# ExpectoPatronum10.net
KiCad netlist of a schematic drawn in EAGLE
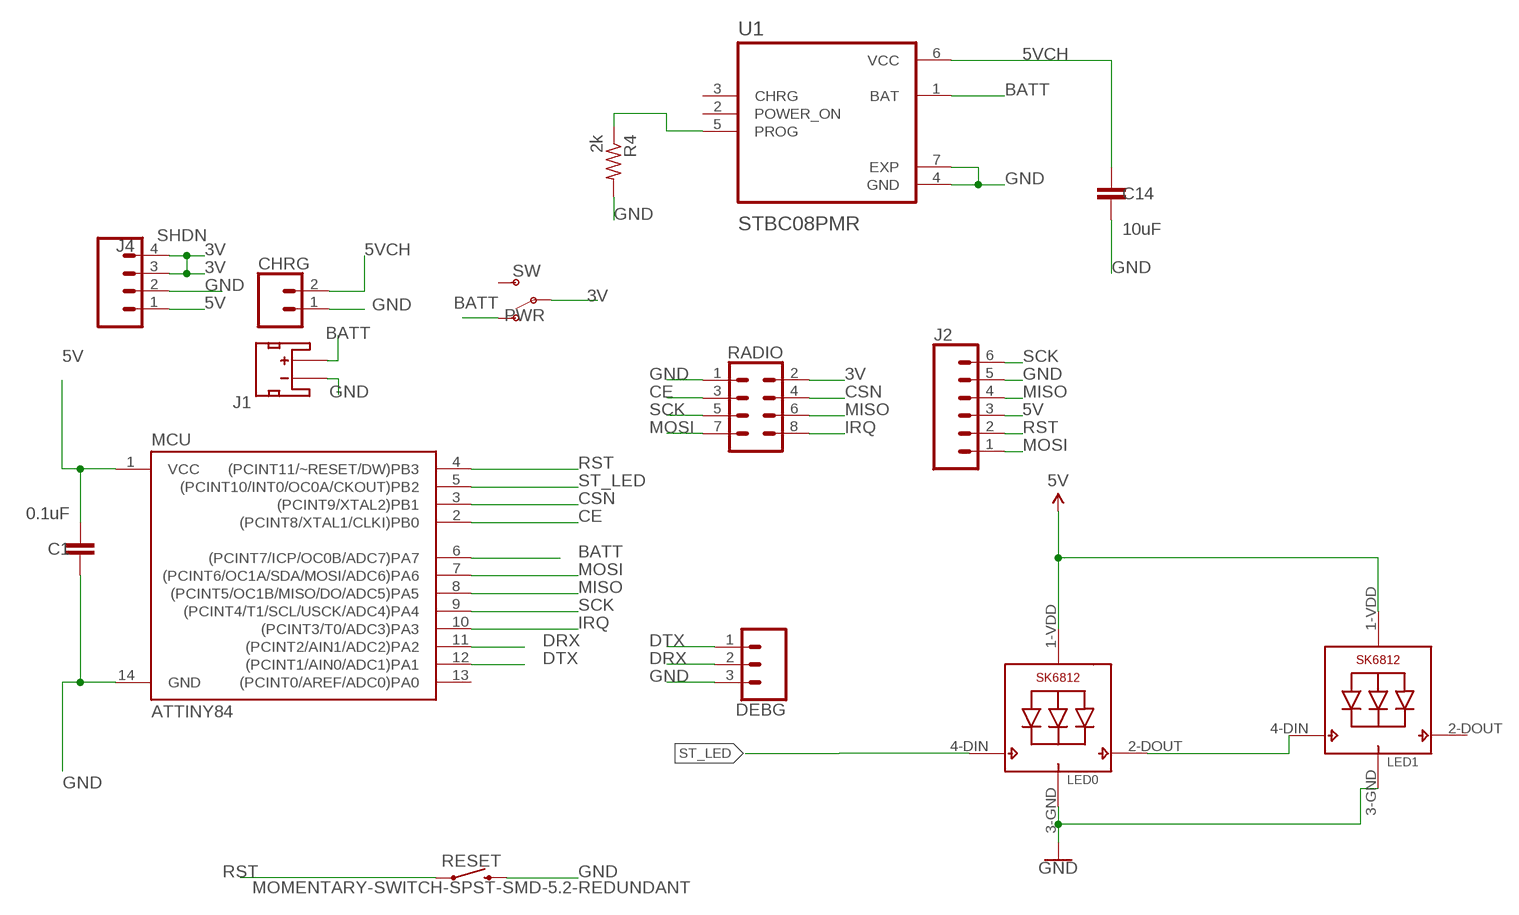
[diagram p0: schematic, sheet 1]

(export (version "E")
  (design (tool "Eeschema 10.0.6"))
  (components
    (comp (ref "C1")
      (value "0.1uF")
      (footprint "eagle-import:0603")
      (libsource (lib "eagle-import") (part "0.1UF-0603-25V-5%"))
    )
    (comp (ref "C14")
      (value "10uF")
      (footprint "eagle-import:0603")
      (libsource (lib "eagle-import") (part "10UF-0603-6.3V-20%"))
    )
    (comp (ref "CHRG")
      (value "CONN_02")
      (footprint "eagle-import:1X02")
      (libsource (lib "eagle-import") (part "CONN_02"))
    )
    (comp (ref "DEBG")
      (value "CONN_03")
      (footprint "eagle-import:1X03")
      (libsource (lib "eagle-import") (part "CONN_03"))
    )
    (comp (ref "J1")
      (value "JST_2MM_MALE")
      (footprint "eagle-import:JST-2-SMD")
      (libsource (lib "eagle-import") (part "JST_2MM_MALE"))
    )
    (comp (ref "J2")
      (value "CONN_06NO_SILK_FEMALE_PTH")
      (footprint "eagle-import:1X06_NO_SILK")
      (libsource (lib "eagle-import") (part "CONN_06NO_SILK_FEMALE_PTH"))
    )
    (comp (ref "J4")
      (value "CONN_04")
      (footprint "eagle-import:1X04")
      (libsource (lib "eagle-import") (part "CONN_04"))
    )
    (comp (ref "LED0")
      (value "SK6812_5050W")
      (footprint "eagle-import:LED5050_W")
      (libsource (lib "eagle-import") (part "SK6812_5050W"))
    )
    (comp (ref "LED1")
      (value "SK6812_5050W")
      (footprint "eagle-import:LED5050_W")
      (libsource (lib "eagle-import") (part "SK6812_5050W"))
    )
    (comp (ref "MCU")
      (value "ATTINY84")
      (footprint "eagle-import:SO14")
      (libsource (lib "eagle-import") (part "ATTINY84"))
    )
    (comp (ref "PWR")
      (value "SW")
      (footprint "eagle-import:SWITCH_SPST_SMD_A")
      (libsource (lib "eagle-import") (part "SWITCH-SPDT-SMD-RIGHT-ANGLE"))
    )
    (comp (ref "R4")
      (value "2k")
      (footprint "eagle-import:R0603")
      (libsource (lib "eagle-import") (part "R-US_R0603"))
    )
    (comp (ref "RADIO")
      (value "CONN_04X2")
      (footprint "eagle-import:2X4")
      (libsource (lib "eagle-import") (part "CONN_04X2"))
    )
    (comp (ref "RESET")
      (value "MOMENTARY-SWITCH-SPST-SMD-5.2-REDUNDANT")
      (footprint "eagle-import:TACTILE_SWITCH_SMD_5.2MM")
      (libsource (lib "eagle-import") (part "MOMENTARY-SWITCH-SPST-SMD-5.2-REDUNDANT"))
    )
    (comp (ref "U1")
      (value "STBC08PMR")
      (footprint "eagle-import:SON95P300X300X100-7N")
      (fields (field (name "DIGI-KEY_PART_NUMBER") "497-5808-1-ND") (field (name "MF") "STMicroelectronics"))
      (libsource (lib "eagle-import") (part "STBC08PMR"))
    )
  )
  (nets
    (net (code "1") (name "/3V") (class "Default")
      (node (ref "J4") (pin "3") (pinfunction "3_3") (pintype "passive"))
      (node (ref "J4") (pin "4") (pinfunction "4_4") (pintype "passive"))
      (node (ref "PWR") (pin "2") (pinfunction "P_2") (pintype "passive"))
      (node (ref "RADIO") (pin "2") (pinfunction "2_2") (pintype "passive"))
    )
    (net (code "2") (name "/5VCH") (class "Default")
      (node (ref "C14") (pin "1") (pinfunction "1_1") (pintype "passive"))
      (node (ref "CHRG") (pin "2") (pinfunction "2_2") (pintype "passive"))
      (node (ref "U1") (pin "6") (pinfunction "VCC_6") (pintype "power_in"))
    )
    (net (code "3") (name "/BATT") (class "Default")
      (node (ref "J1") (pin "2") (pinfunction "+_2") (pintype "bidirectional"))
      (node (ref "MCU") (pin "6") (pinfunction "(PCINT7/ICP/OC0B/ADC7)PA7_6") (pintype "bidirectional"))
      (node (ref "PWR") (pin "1") (pinfunction "O_1") (pintype "passive"))
      (node (ref "U1") (pin "1") (pinfunction "BAT_1") (pintype "output"))
    )
    (net (code "4") (name "/CE") (class "Default")
      (node (ref "MCU") (pin "2") (pinfunction "(PCINT8/XTAL1/CLKI)PB0_2") (pintype "bidirectional"))
      (node (ref "RADIO") (pin "3") (pinfunction "3_3") (pintype "passive"))
    )
    (net (code "5") (name "/CSN") (class "Default")
      (node (ref "MCU") (pin "3") (pinfunction "(PCINT9/XTAL2)PB1_3") (pintype "bidirectional"))
      (node (ref "RADIO") (pin "4") (pinfunction "4_4") (pintype "passive"))
    )
    (net (code "6") (name "/DRX") (class "Default")
      (node (ref "DEBG") (pin "2") (pinfunction "2_2") (pintype "passive"))
      (node (ref "MCU") (pin "11") (pinfunction "(PCINT2/AIN1/ADC2)PA2_11") (pintype "bidirectional"))
    )
    (net (code "7") (name "/DTX") (class "Default")
      (node (ref "DEBG") (pin "1") (pinfunction "1_1") (pintype "passive"))
      (node (ref "MCU") (pin "12") (pinfunction "(PCINT1/AIN0/ADC1)PA1_12") (pintype "bidirectional"))
    )
    (net (code "8") (name "/IRQ") (class "Default")
      (node (ref "MCU") (pin "10") (pinfunction "(PCINT3/T0/ADC3)PA3_10") (pintype "bidirectional"))
      (node (ref "RADIO") (pin "8") (pinfunction "8_8") (pintype "passive"))
    )
    (net (code "9") (name "/MISO") (class "Default")
      (node (ref "J2") (pin "4") (pinfunction "4_4") (pintype "passive"))
      (node (ref "MCU") (pin "8") (pinfunction "(PCINT5/OC1B/MISO/DO/ADC5)PA5_8") (pintype "bidirectional"))
      (node (ref "RADIO") (pin "6") (pinfunction "6_6") (pintype "passive"))
    )
    (net (code "10") (name "/MOSI") (class "Default")
      (node (ref "J2") (pin "1") (pinfunction "1_1") (pintype "passive"))
      (node (ref "MCU") (pin "7") (pinfunction "(PCINT6/OC1A/SDA/MOSI/ADC6)PA6_7") (pintype "bidirectional"))
      (node (ref "RADIO") (pin "7") (pinfunction "7_7") (pintype "passive"))
    )
    (net (code "11") (name "/RST") (class "Default")
      (node (ref "J2") (pin "2") (pinfunction "2_2") (pintype "passive"))
      (node (ref "MCU") (pin "4") (pinfunction "(PCINT11/~{RESET/DW})PB3_4") (pintype "bidirectional"))
      (node (ref "RESET") (pin "1") (pinfunction "1_1") (pintype "passive"))
      (node (ref "RESET") (pin "2") (pinfunction "1_2") (pintype "passive"))
    )
    (net (code "12") (name "/SCK") (class "Default")
      (node (ref "J2") (pin "6") (pinfunction "6_6") (pintype "passive"))
      (node (ref "MCU") (pin "9") (pinfunction "(PCINT4/T1/SCL/USCK/ADC4)PA4_9") (pintype "bidirectional"))
      (node (ref "RADIO") (pin "5") (pinfunction "5_5") (pintype "passive"))
    )
    (net (code "13") (name "5V") (class "Default")
      (node (ref "C1") (pin "2") (pinfunction "2_2") (pintype "passive"))
      (node (ref "J2") (pin "3") (pinfunction "3_3") (pintype "passive"))
      (node (ref "J4") (pin "1") (pinfunction "1_1") (pintype "passive"))
      (node (ref "LED0") (pin "1-VDD") (pinfunction "VDD_1-VDD") (pintype "power_in"))
      (node (ref "LED1") (pin "1-VDD") (pinfunction "VDD_1-VDD") (pintype "power_in"))
      (node (ref "MCU") (pin "1") (pinfunction "VCC_1") (pintype "bidirectional"))
    )
    (net (code "14") (name "GND") (class "Default")
      (node (ref "C1") (pin "1") (pinfunction "1_1") (pintype "passive"))
      (node (ref "C14") (pin "2") (pinfunction "2_2") (pintype "passive"))
      (node (ref "CHRG") (pin "1") (pinfunction "1_1") (pintype "passive"))
      (node (ref "DEBG") (pin "3") (pinfunction "3_3") (pintype "passive"))
      (node (ref "J1") (pin "1") (pinfunction "-_1") (pintype "bidirectional"))
      (node (ref "J2") (pin "5") (pinfunction "5_5") (pintype "passive"))
      (node (ref "J4") (pin "2") (pinfunction "2_2") (pintype "passive"))
      (node (ref "LED0") (pin "3-GND") (pinfunction "GND_3-GND") (pintype "power_in"))
      (node (ref "LED1") (pin "3-GND") (pinfunction "GND_3-GND") (pintype "power_in"))
      (node (ref "MCU") (pin "14") (pinfunction "GND_14") (pintype "bidirectional"))
      (node (ref "R4") (pin "2") (pinfunction "2_2") (pintype "passive"))
      (node (ref "RADIO") (pin "1") (pinfunction "1_1") (pintype "passive"))
      (node (ref "RESET") (pin "3") (pinfunction "2_3") (pintype "passive"))
      (node (ref "RESET") (pin "4") (pinfunction "2_4") (pintype "passive"))
      (node (ref "U1") (pin "4") (pinfunction "GND_4") (pintype "power_in"))
      (node (ref "U1") (pin "7") (pinfunction "EXP_7") (pintype "power_in"))
    )
    (net (code "15") (name "Net-(LED0-DO)") (class "Default")
      (node (ref "LED0") (pin "2-DOUT") (pinfunction "DO_2-DOUT") (pintype "output"))
      (node (ref "LED1") (pin "4-DIN") (pinfunction "DI_4-DIN") (pintype "input"))
    )
    (net (code "16") (name "Net-(U1-PROG)") (class "Default")
      (node (ref "R4") (pin "1") (pinfunction "1_1") (pintype "passive"))
      (node (ref "U1") (pin "5") (pinfunction "PROG_5") (pintype "bidirectional"))
    )
    (net (code "17") (name "ST_LED") (class "Default")
      (node (ref "LED0") (pin "4-DIN") (pinfunction "DI_4-DIN") (pintype "input"))
      (node (ref "MCU") (pin "5") (pinfunction "(PCINT10/INT0/OC0A/CKOUT)PB2_5") (pintype "bidirectional"))
    )
    (net (code "18") (name "unconnected-(J1-PAD1-PadNC1)") (class "Default")
      (node (ref "J1") (pin "NC1") (pinfunction "PAD1_NC1") (pintype "bidirectional"))
    )
    (net (code "19") (name "unconnected-(J1-PAD2-PadNC2)") (class "Default")
      (node (ref "J1") (pin "NC2") (pinfunction "PAD2_NC2") (pintype "bidirectional"))
    )
    (net (code "20") (name "unconnected-(LED1-DO-Pad2-DOUT)") (class "Default")
      (node (ref "LED1") (pin "2-DOUT") (pinfunction "DO_2-DOUT") (pintype "output"))
    )
    (net (code "21") (name "unconnected-(MCU-(PCINT0{slash}AREF{slash}ADC0)PA0-Pad13)") (class "Default")
      (node (ref "MCU") (pin "13") (pinfunction "(PCINT0/AREF/ADC0)PA0_13") (pintype "bidirectional"))
    )
    (net (code "22") (name "unconnected-(PWR-S-Pad3)") (class "Default")
      (node (ref "PWR") (pin "3") (pinfunction "S_3") (pintype "passive"))
    )
    (net (code "23") (name "unconnected-(U1-CHRG-Pad3)") (class "Default")
      (node (ref "U1") (pin "3") (pinfunction "CHRG_3") (pintype "bidirectional"))
    )
    (net (code "24") (name "unconnected-(U1-POWER_ON-Pad2)") (class "Default")
      (node (ref "U1") (pin "2") (pinfunction "POWER_ON_2") (pintype "bidirectional"))
    )
  )
)
